# Power.net
KiCad netlist of a schematic drawn in Altium Designer
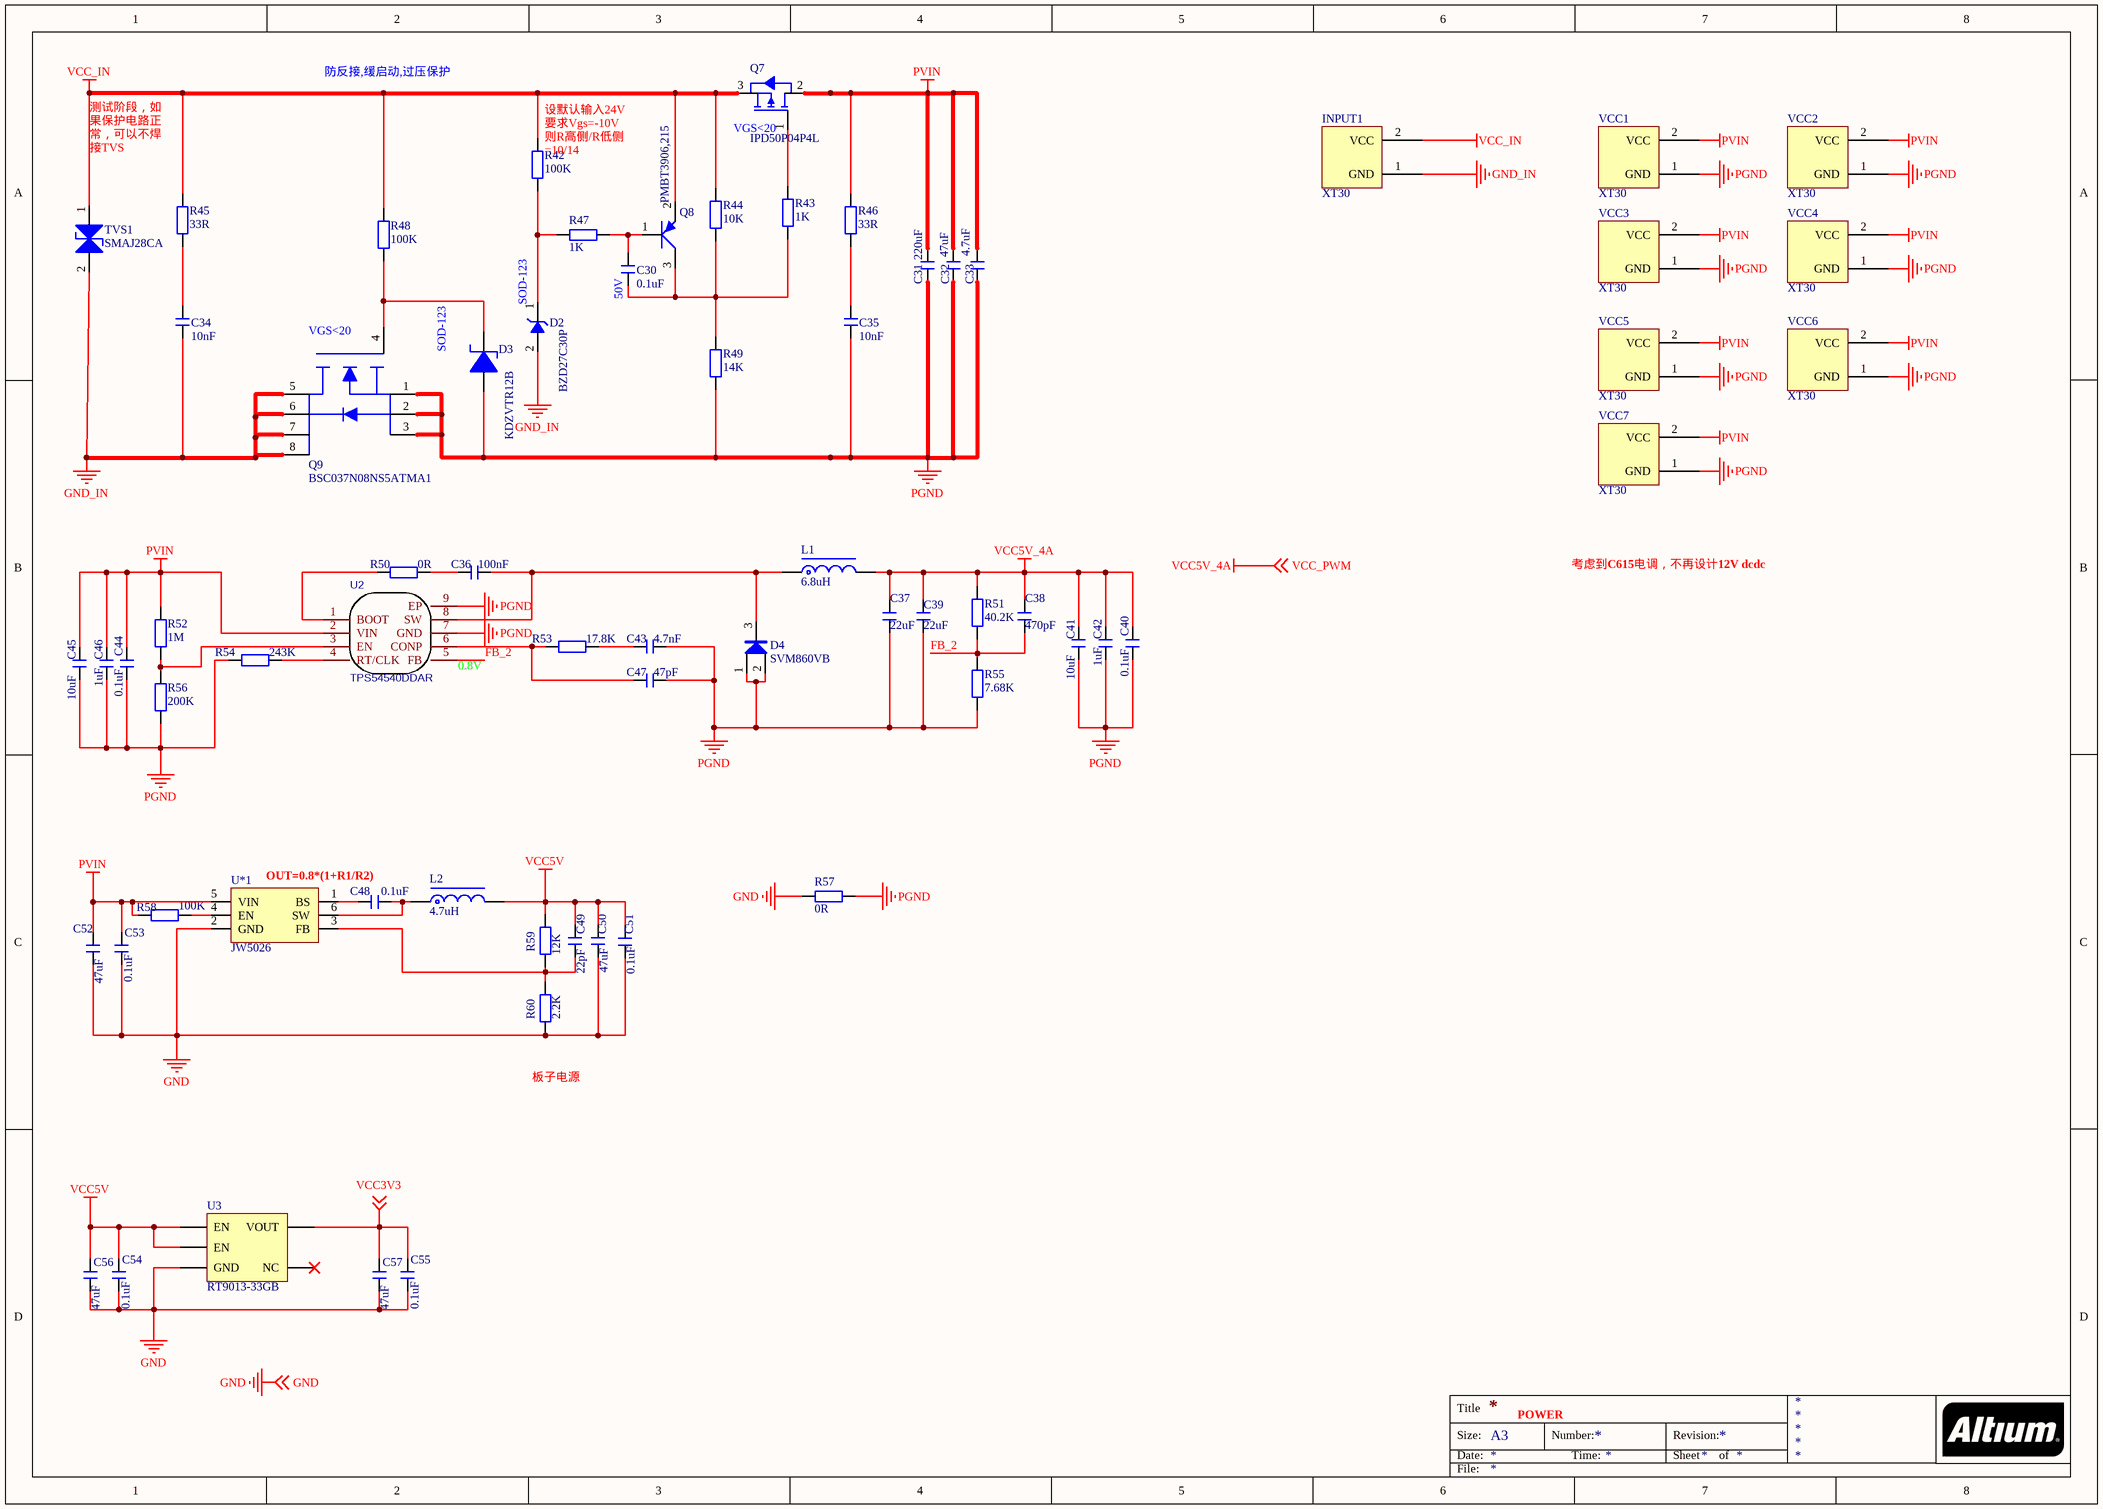
[diagram p0: Power.SchDoc]

(export (version "E")
  (design (tool "Eeschema 10.0.6"))
  (components
    (comp (ref "C30")
      (value "0.1uF")
      (footprint "C 0603_L")
      (description "贴片电容")
      (libsource (lib "0.1 - 电阻-电容-电感") (part "C"))
    )
    (comp (ref "C31")
      (value "220uF")
      (footprint "C 1206_L")
      (description "贴片电容")
      (libsource (lib "0.1 - 电阻-电容-电感") (part "C"))
    )
    (comp (ref "C32")
      (value "47uF")
      (footprint "C 1206_L")
      (description "贴片电容")
      (libsource (lib "0.1 - 电阻-电容-电感") (part "C"))
    )
    (comp (ref "C33")
      (value "4.7uF")
      (footprint "C 1206_L")
      (description "贴片电容")
      (libsource (lib "0.1 - 电阻-电容-电感") (part "C"))
    )
    (comp (ref "C34")
      (value "10nF")
      (footprint "C 0603_L")
      (description "贴片电容")
      (libsource (lib "0.1 - 电阻-电容-电感") (part "C"))
    )
    (comp (ref "C35")
      (value "10nF")
      (footprint "C 0603_L")
      (description "贴片电容")
      (libsource (lib "0.1 - 电阻-电容-电感") (part "C"))
    )
    (comp (ref "C36")
      (value "100nF")
      (footprint "C 0603_L")
      (description "贴片电容")
      (libsource (lib "0.1 - 电阻-电容-电感") (part "C"))
    )
    (comp (ref "C37")
      (value "22uF")
      (footprint "C 0805_L")
      (description "贴片电容")
      (libsource (lib "0.1 - 电阻-电容-电感") (part "C"))
    )
    (comp (ref "C38")
      (value "470pF")
      (footprint "C 0603_L")
      (description "贴片电容")
      (libsource (lib "0.1 - 电阻-电容-电感") (part "C"))
    )
    (comp (ref "C39")
      (value "22uF")
      (footprint "C 0805_L")
      (description "贴片电容")
      (libsource (lib "0.1 - 电阻-电容-电感") (part "C"))
    )
    (comp (ref "C40")
      (value "0.1uF")
      (footprint "C 0805_L")
      (description "贴片电容")
      (libsource (lib "0.1 - 电阻-电容-电感") (part "C"))
    )
    (comp (ref "C41")
      (value "10uF")
      (footprint "C 0805_L")
      (description "贴片电容")
      (libsource (lib "0.1 - 电阻-电容-电感") (part "C"))
    )
    (comp (ref "C42")
      (value "1uF")
      (footprint "C 0805_L")
      (description "贴片电容")
      (libsource (lib "0.1 - 电阻-电容-电感") (part "C"))
    )
    (comp (ref "C43")
      (value "4.7nF")
      (footprint "C 0603_L")
      (description "贴片电容")
      (libsource (lib "0.1 - 电阻-电容-电感") (part "C"))
    )
    (comp (ref "C44")
      (value "0.1uF")
      (footprint "C 0805_L")
      (description "贴片电容")
      (libsource (lib "0.1 - 电阻-电容-电感") (part "C"))
    )
    (comp (ref "C45")
      (value "10uF")
      (footprint "C 0805_L")
      (description "贴片电容")
      (libsource (lib "0.1 - 电阻-电容-电感") (part "C"))
    )
    (comp (ref "C46")
      (value "1uF")
      (footprint "C 0805_L")
      (description "贴片电容")
      (libsource (lib "0.1 - 电阻-电容-电感") (part "C"))
    )
    (comp (ref "C47")
      (value "47pF")
      (footprint "C 0603_L")
      (description "贴片电容")
      (libsource (lib "0.1 - 电阻-电容-电感") (part "C"))
    )
    (comp (ref "C48")
      (value "0.1uF")
      (footprint "C 0603_L")
      (description "贴片电容")
      (libsource (lib "0.1 - 电阻-电容-电感") (part "C"))
    )
    (comp (ref "C49")
      (value "22pF")
      (footprint "C 0603_L")
      (description "贴片电容")
      (libsource (lib "0.1 - 电阻-电容-电感") (part "C"))
    )
    (comp (ref "C50")
      (value "47uF")
      (footprint "C 0805_L")
      (description "贴片电容")
      (libsource (lib "0.1 - 电阻-电容-电感") (part "C"))
    )
    (comp (ref "C51")
      (value "0.1uF")
      (footprint "C 0805_L")
      (description "贴片电容")
      (libsource (lib "0.1 - 电阻-电容-电感") (part "C"))
    )
    (comp (ref "C52")
      (value "47uF")
      (footprint "C 0805_L")
      (description "贴片电容")
      (libsource (lib "0.1 - 电阻-电容-电感") (part "C"))
    )
    (comp (ref "C53")
      (value "0.1uF")
      (footprint "C 0805_L")
      (description "贴片电容")
      (libsource (lib "0.1 - 电阻-电容-电感") (part "C"))
    )
    (comp (ref "C54")
      (value "0.1uF")
      (footprint "C 0805_L")
      (description "贴片电容")
      (libsource (lib "0.1 - 电阻-电容-电感") (part "C"))
    )
    (comp (ref "C55")
      (value "0.1uF")
      (footprint "C 0805_L")
      (description "贴片电容")
      (libsource (lib "0.1 - 电阻-电容-电感") (part "C"))
    )
    (comp (ref "C56")
      (value "47uF")
      (footprint "C 0805_L")
      (description "贴片电容")
      (libsource (lib "0.1 - 电阻-电容-电感") (part "C"))
    )
    (comp (ref "C57")
      (value "47uF")
      (footprint "C 0805_L")
      (description "贴片电容")
      (libsource (lib "0.1 - 电阻-电容-电感") (part "C"))
    )
    (comp (ref "D2")
      (value "BZD27C30P")
      (footprint "mx_pcb_library:SOD-123_L2.8-W1.8-LS3.7-RD")
      (libsource (lib "mx_pcb_library") (part "BZD27C30P"))
    )
    (comp (ref "D3")
      (value "KDZVTR12B")
      (footprint "mx_pcb_library:SOD-123_L2.8-W1.8-LS3.7-RD")
      (libsource (lib "mx_pcb_library") (part "KDZVTR12B"))
    )
    (comp (ref "D4")
      (value "SVM860VB")
      (footprint "1.30-二极管-整流桥堆:TO-277B_3P-L6.1-W4.3-LS7.0-BR")
      (description "TO-277B系列,SVM860VB-8A")
      (libsource (lib "0.2 -  二极管-整流桥") (part "SVM860VB"))
    )
    (comp (ref "INPUT1")
      (value "XT30")
      (footprint "mx_pcb_library:XT30PW-M")
      (libsource (lib "mx_pcb_library") (part "XT30"))
    )
    (comp (ref "L1")
      (value "6.8uH")
      (footprint "CDRH73")
      (description "功率屏蔽电感")
      (libsource (lib "0.1 - 电阻-电容-电感") (part "L-CDRH"))
    )
    (comp (ref "L2")
      (value "4.7uH")
      (footprint "CD53")
      (description "CD系列贴片线绕功率电感")
      (libsource (lib "0.1 - 电阻-电容-电感") (part "L-SMD"))
    )
    (comp (ref "Q7")
      (value "IPD50P04P4L")
      (footprint "mx_pcb_library:PG-TO252-3")
      (libsource (lib "mx_pcb_library") (part "IPD50P04P4L"))
    )
    (comp (ref "Q8")
      (value "PMBT3906,215")
      (footprint "mx_pcb_library:SOT-23-3_L2.9-W1.3-P1.90-LS2.4-BR")
      (libsource (lib "mx_pcb_library") (part "PMBT3906,215"))
    )
    (comp (ref "Q9")
      (value "BSC037N08NS5ATMA1")
      (footprint "mx_pcb_library:PG-TDSON-8_L5.0-W6.0-P1.27-LS6.2-BL-EP")
      (libsource (lib "mx_pcb_library") (part "BSC037N08NS5ATMA1"))
    )
    (comp (ref "R42")
      (value "100K")
      (footprint "R 0603_L")
      (description "贴片电阻")
      (libsource (lib "0.1 - 电阻-电容-电感") (part "R"))
    )
    (comp (ref "R43")
      (value "1K")
      (footprint "R 0603_L")
      (description "贴片电阻")
      (libsource (lib "0.1 - 电阻-电容-电感") (part "R"))
    )
    (comp (ref "R44")
      (value "10K")
      (footprint "R 0603_L")
      (description "贴片电阻")
      (libsource (lib "0.1 - 电阻-电容-电感") (part "R"))
    )
    (comp (ref "R45")
      (value "33R")
      (footprint "R 0603_L")
      (description "贴片电阻")
      (libsource (lib "0.1 - 电阻-电容-电感") (part "R"))
    )
    (comp (ref "R46")
      (value "33R")
      (footprint "R 0603_L")
      (description "贴片电阻")
      (libsource (lib "0.1 - 电阻-电容-电感") (part "R"))
    )
    (comp (ref "R47")
      (value "1K")
      (footprint "R 0603_L")
      (description "贴片电阻")
      (libsource (lib "0.1 - 电阻-电容-电感") (part "R"))
    )
    (comp (ref "R48")
      (value "100K")
      (footprint "R 0603_L")
      (description "贴片电阻")
      (libsource (lib "0.1 - 电阻-电容-电感") (part "R"))
    )
    (comp (ref "R49")
      (value "14K")
      (footprint "R 0603_L")
      (description "贴片电阻")
      (libsource (lib "0.1 - 电阻-电容-电感") (part "R"))
    )
    (comp (ref "R50")
      (value "0R")
      (footprint "R 0603_L")
      (description "贴片电阻")
      (libsource (lib "0.1 - 电阻-电容-电感") (part "R"))
    )
    (comp (ref "R51")
      (value "40.2K")
      (footprint "R 0603_L")
      (description "贴片电阻")
      (libsource (lib "0.1 - 电阻-电容-电感") (part "R"))
    )
    (comp (ref "R52")
      (value "1M")
      (footprint "R 0603_L")
      (description "贴片电阻")
      (libsource (lib "0.1 - 电阻-电容-电感") (part "R"))
    )
    (comp (ref "R53")
      (value "17.8K")
      (footprint "R 0603_L")
      (description "贴片电阻")
      (libsource (lib "0.1 - 电阻-电容-电感") (part "R"))
    )
    (comp (ref "R54")
      (value "243K")
      (footprint "R 0603_L")
      (description "贴片电阻")
      (libsource (lib "0.1 - 电阻-电容-电感") (part "R"))
    )
    (comp (ref "R55")
      (value "7.68K")
      (footprint "R 0603_L")
      (description "贴片电阻")
      (libsource (lib "0.1 - 电阻-电容-电感") (part "R"))
    )
    (comp (ref "R56")
      (value "200K")
      (footprint "R 0603_L")
      (description "贴片电阻")
      (libsource (lib "0.1 - 电阻-电容-电感") (part "R"))
    )
    (comp (ref "R57")
      (value "0R")
      (footprint "R 0603_L")
      (description "贴片电阻")
      (libsource (lib "0.1 - 电阻-电容-电感") (part "R"))
    )
    (comp (ref "R58")
      (value "100K")
      (footprint "R 0603_L")
      (description "贴片电阻")
      (libsource (lib "0.1 - 电阻-电容-电感") (part "R"))
    )
    (comp (ref "R59")
      (value "12K")
      (footprint "R 0603_L")
      (description "贴片电阻")
      (libsource (lib "0.1 - 电阻-电容-电感") (part "R"))
    )
    (comp (ref "R60")
      (value "2.2K")
      (footprint "R 0603_L")
      (description "贴片电阻")
      (libsource (lib "0.1 - 电阻-电容-电感") (part "R"))
    )
    (comp (ref "TVS1")
      (value "SMAJ28CA")
      (footprint "mx_pcb_library:SMA(DO-214AC)")
      (libsource (lib "mx_pcb_library") (part "SMAJ28CA"))
    )
    (comp (ref "U*1")
      (value "JW5026")
      (footprint "SOT-23-6_L2.9-W1.6-P0.95-LS2.8-BL")
      (description "BUCK、MAX40V")
      (libsource (lib "mx_pcb_library") (part "JW5026"))
    )
    (comp (ref "U2")
      (value "TPS54540DDAR")
      (footprint "mx_pcb_library:TPS54540")
      (fields (field (name "BOM_SUPPLIER PART") "C95286"))
      (libsource (lib "mx_pcb_library") (part "TPS54540DDAR"))
    )
    (comp (ref "U3")
      (value "RT9013-33GB")
      (footprint "SOT23-5M")
      (libsource (lib "mx_pcb_library") (part "RT9013-33GB"))
    )
    (comp (ref "VCC1")
      (value "XT30")
      (footprint "mx_pcb_library:XT30UPB-F")
      (libsource (lib "mx_pcb_library") (part "XT30"))
    )
    (comp (ref "VCC2")
      (value "XT30")
      (footprint "mx_pcb_library:XT30UPB-F")
      (libsource (lib "mx_pcb_library") (part "XT30"))
    )
    (comp (ref "VCC3")
      (value "XT30")
      (footprint "mx_pcb_library:XT30UPB-F")
      (libsource (lib "mx_pcb_library") (part "XT30"))
    )
    (comp (ref "VCC4")
      (value "XT30")
      (footprint "mx_pcb_library:XT30UPB-F")
      (libsource (lib "mx_pcb_library") (part "XT30"))
    )
    (comp (ref "VCC5")
      (value "XT30")
      (footprint "mx_pcb_library:XT30UPB-F")
      (libsource (lib "mx_pcb_library") (part "XT30"))
    )
    (comp (ref "VCC6")
      (value "XT30")
      (footprint "mx_pcb_library:XT30UPB-F")
      (libsource (lib "mx_pcb_library") (part "XT30"))
    )
    (comp (ref "VCC7")
      (value "XT30")
      (footprint "mx_pcb_library:XT30UPB-F")
      (libsource (lib "mx_pcb_library") (part "XT30"))
    )
  )
  (nets
    (net (code "1") (name "/FB_2") (class "Default")
      (node (ref "C38") (pin "1") (pinfunction "1_1") (pintype "passive"))
      (node (ref "R51") (pin "1") (pinfunction "1_1") (pintype "passive"))
      (node (ref "R55") (pin "2") (pinfunction "2_2") (pintype "passive"))
      (node (ref "U2") (pin "5") (pinfunction "FB_5") (pintype "passive"))
    )
    (net (code "2") (name "GND") (class "Default")
      (node (ref "C50") (pin "1") (pinfunction "1_1") (pintype "passive"))
      (node (ref "C51") (pin "1") (pinfunction "1_1") (pintype "passive"))
      (node (ref "C52") (pin "1") (pinfunction "1_1") (pintype "passive"))
      (node (ref "C53") (pin "1") (pinfunction "1_1") (pintype "passive"))
      (node (ref "C54") (pin "1") (pinfunction "1_1") (pintype "passive"))
      (node (ref "C55") (pin "1") (pinfunction "1_1") (pintype "passive"))
      (node (ref "C56") (pin "1") (pinfunction "1_1") (pintype "passive"))
      (node (ref "C57") (pin "1") (pinfunction "1_1") (pintype "passive"))
      (node (ref "R57") (pin "1") (pinfunction "1_1") (pintype "passive"))
      (node (ref "R60") (pin "1") (pinfunction "1_1") (pintype "passive"))
      (node (ref "U*1") (pin "2") (pinfunction "GND_2") (pintype "passive"))
      (node (ref "U3") (pin "2") (pinfunction "GND_2") (pintype "passive"))
    )
    (net (code "3") (name "GND_IN") (class "Default")
      (node (ref "C34") (pin "1") (pinfunction "1_1") (pintype "passive"))
      (node (ref "D2") (pin "2") (pinfunction "2_2") (pintype "passive"))
      (node (ref "INPUT1") (pin "1") (pinfunction "GND_1") (pintype "passive"))
      (node (ref "Q9") (pin "5") (pinfunction "5_5") (pintype "passive"))
      (node (ref "Q9") (pin "6") (pinfunction "6_6") (pintype "passive"))
      (node (ref "Q9") (pin "7") (pinfunction "7_7") (pintype "passive"))
      (node (ref "Q9") (pin "8") (pinfunction "8_8") (pintype "passive"))
      (node (ref "TVS1") (pin "2") (pinfunction "2_2") (pintype "passive"))
    )
    (net (code "4") (name "Net-(C30-Pad1)") (class "Default")
      (node (ref "C30") (pin "1") (pinfunction "1_1") (pintype "passive"))
      (node (ref "Q8") (pin "3") (pinfunction "3_3") (pintype "passive"))
      (node (ref "R43") (pin "1") (pinfunction "1_1") (pintype "passive"))
      (node (ref "R44") (pin "1") (pinfunction "1_1") (pintype "passive"))
      (node (ref "R49") (pin "2") (pinfunction "2_2") (pintype "passive"))
    )
    (net (code "5") (name "Net-(C30-Pad2)") (class "Default")
      (node (ref "C30") (pin "2") (pinfunction "2_2") (pintype "passive"))
      (node (ref "Q8") (pin "1") (pinfunction "1_1") (pintype "passive"))
      (node (ref "R47") (pin "1") (pinfunction "1_1") (pintype "passive"))
    )
    (net (code "6") (name "Net-(C34-Pad2)") (class "Default")
      (node (ref "C34") (pin "2") (pinfunction "2_2") (pintype "passive"))
      (node (ref "R45") (pin "1") (pinfunction "1_1") (pintype "passive"))
    )
    (net (code "7") (name "Net-(C35-Pad2)") (class "Default")
      (node (ref "C35") (pin "2") (pinfunction "2_2") (pintype "passive"))
      (node (ref "R46") (pin "1") (pinfunction "1_1") (pintype "passive"))
    )
    (net (code "8") (name "Net-(C36-Pad1)") (class "Default")
      (node (ref "C36") (pin "1") (pinfunction "1_1") (pintype "passive"))
      (node (ref "R50") (pin "1") (pinfunction "1_1") (pintype "passive"))
    )
    (net (code "9") (name "Net-(C43-Pad1)") (class "Default")
      (node (ref "C43") (pin "1") (pinfunction "1_1") (pintype "passive"))
      (node (ref "R53") (pin "1") (pinfunction "1_1") (pintype "passive"))
    )
    (net (code "10") (name "Net-(D2-Pad1)") (class "Default")
      (node (ref "D2") (pin "1") (pinfunction "1_1") (pintype "passive"))
      (node (ref "R42") (pin "1") (pinfunction "1_1") (pintype "passive"))
      (node (ref "R47") (pin "2") (pinfunction "2_2") (pintype "passive"))
    )
    (net (code "11") (name "Net-(D3-Pad1)") (class "Default")
      (node (ref "D3") (pin "1") (pinfunction "1_1") (pintype "passive"))
      (node (ref "Q9") (pin "4") (pinfunction "4_4") (pintype "passive"))
      (node (ref "R48") (pin "1") (pinfunction "1_1") (pintype "passive"))
    )
    (net (code "12") (name "Net-(Q7-Pad1)") (class "Default")
      (node (ref "Q7") (pin "1") (pinfunction "1_1") (pintype "passive"))
      (node (ref "R43") (pin "2") (pinfunction "2_2") (pintype "passive"))
    )
    (net (code "13") (name "Net-(U*1-BS)") (class "Default")
      (node (ref "C48") (pin "1") (pinfunction "1_1") (pintype "passive"))
      (node (ref "U*1") (pin "1") (pinfunction "BS_1") (pintype "passive"))
    )
    (net (code "14") (name "Net-(U*1-EN)") (class "Default")
      (node (ref "R58") (pin "1") (pinfunction "1_1") (pintype "passive"))
      (node (ref "U*1") (pin "4") (pinfunction "EN_4") (pintype "passive"))
    )
    (net (code "15") (name "Net-(U*1-FB)") (class "Default")
      (node (ref "C49") (pin "1") (pinfunction "1_1") (pintype "passive"))
      (node (ref "R59") (pin "1") (pinfunction "1_1") (pintype "passive"))
      (node (ref "R60") (pin "2") (pinfunction "2_2") (pintype "passive"))
      (node (ref "U*1") (pin "3") (pinfunction "FB_3") (pintype "passive"))
    )
    (net (code "16") (name "Net-(U*1-SW)") (class "Default")
      (node (ref "C48") (pin "2") (pinfunction "2_2") (pintype "passive"))
      (node (ref "L2") (pin "1") (pinfunction "1_1") (pintype "passive"))
      (node (ref "U*1") (pin "6") (pinfunction "SW_6") (pintype "passive"))
    )
    (net (code "17") (name "Net-(U2-BOOT)") (class "Default")
      (node (ref "R50") (pin "2") (pinfunction "2_2") (pintype "passive"))
      (node (ref "U2") (pin "1") (pinfunction "BOOT_1") (pintype "passive"))
    )
    (net (code "18") (name "Net-(U2-CONP)") (class "Default")
      (node (ref "C47") (pin "1") (pinfunction "1_1") (pintype "passive"))
      (node (ref "R53") (pin "2") (pinfunction "2_2") (pintype "passive"))
      (node (ref "U2") (pin "6") (pinfunction "CONP_6") (pintype "passive"))
    )
    (net (code "19") (name "Net-(U2-EN)") (class "Default")
      (node (ref "R52") (pin "1") (pinfunction "1_1") (pintype "passive"))
      (node (ref "R56") (pin "2") (pinfunction "2_2") (pintype "passive"))
      (node (ref "U2") (pin "3") (pinfunction "EN_3") (pintype "passive"))
    )
    (net (code "20") (name "Net-(U2-RT{slash}CLK)") (class "Default")
      (node (ref "R54") (pin "1") (pinfunction "1_1") (pintype "passive"))
      (node (ref "U2") (pin "4") (pinfunction "RT/CLK_4") (pintype "passive"))
    )
    (net (code "21") (name "Net-(U2-SW)") (class "Default")
      (node (ref "C36") (pin "2") (pinfunction "2_2") (pintype "passive"))
      (node (ref "D4") (pin "3") (pinfunction "3_3") (pintype "passive"))
      (node (ref "L1") (pin "1") (pinfunction "1_1") (pintype "passive"))
      (node (ref "U2") (pin "8") (pinfunction "SW_8") (pintype "passive"))
    )
    (net (code "22") (name "PGND") (class "Default")
      (node (ref "C31") (pin "1") (pinfunction "1_1") (pintype "passive"))
      (node (ref "C32") (pin "1") (pinfunction "1_1") (pintype "passive"))
      (node (ref "C33") (pin "1") (pinfunction "1_1") (pintype "passive"))
      (node (ref "C35") (pin "1") (pinfunction "1_1") (pintype "passive"))
      (node (ref "C37") (pin "1") (pinfunction "1_1") (pintype "passive"))
      (node (ref "C39") (pin "1") (pinfunction "1_1") (pintype "passive"))
      (node (ref "C40") (pin "1") (pinfunction "1_1") (pintype "passive"))
      (node (ref "C41") (pin "1") (pinfunction "1_1") (pintype "passive"))
      (node (ref "C42") (pin "1") (pinfunction "1_1") (pintype "passive"))
      (node (ref "C43") (pin "2") (pinfunction "2_2") (pintype "passive"))
      (node (ref "C44") (pin "1") (pinfunction "1_1") (pintype "passive"))
      (node (ref "C45") (pin "1") (pinfunction "1_1") (pintype "passive"))
      (node (ref "C46") (pin "1") (pinfunction "1_1") (pintype "passive"))
      (node (ref "C47") (pin "2") (pinfunction "2_2") (pintype "passive"))
      (node (ref "D3") (pin "2") (pinfunction "2_2") (pintype "passive"))
      (node (ref "D4") (pin "1") (pinfunction "A_1") (pintype "passive"))
      (node (ref "D4") (pin "2") (pinfunction "K_2") (pintype "passive"))
      (node (ref "Q9") (pin "1") (pinfunction "1_1") (pintype "passive"))
      (node (ref "Q9") (pin "2") (pinfunction "2_2") (pintype "passive"))
      (node (ref "Q9") (pin "3") (pinfunction "3_3") (pintype "passive"))
      (node (ref "R49") (pin "1") (pinfunction "1_1") (pintype "passive"))
      (node (ref "R54") (pin "2") (pinfunction "2_2") (pintype "passive"))
      (node (ref "R55") (pin "1") (pinfunction "1_1") (pintype "passive"))
      (node (ref "R56") (pin "1") (pinfunction "1_1") (pintype "passive"))
      (node (ref "R57") (pin "2") (pinfunction "2_2") (pintype "passive"))
      (node (ref "U2") (pin "7") (pinfunction "GND_7") (pintype "passive"))
      (node (ref "U2") (pin "9") (pinfunction "EP_9") (pintype "passive"))
      (node (ref "VCC1") (pin "1") (pinfunction "GND_1") (pintype "passive"))
      (node (ref "VCC2") (pin "1") (pinfunction "GND_1") (pintype "passive"))
      (node (ref "VCC3") (pin "1") (pinfunction "GND_1") (pintype "passive"))
      (node (ref "VCC4") (pin "1") (pinfunction "GND_1") (pintype "passive"))
      (node (ref "VCC5") (pin "1") (pinfunction "GND_1") (pintype "passive"))
      (node (ref "VCC6") (pin "1") (pinfunction "GND_1") (pintype "passive"))
      (node (ref "VCC7") (pin "1") (pinfunction "GND_1") (pintype "passive"))
    )
    (net (code "23") (name "PVIN") (class "Default")
      (node (ref "C31") (pin "2") (pinfunction "2_2") (pintype "passive"))
      (node (ref "C32") (pin "2") (pinfunction "2_2") (pintype "passive"))
      (node (ref "C33") (pin "2") (pinfunction "2_2") (pintype "passive"))
      (node (ref "C44") (pin "2") (pinfunction "2_2") (pintype "passive"))
      (node (ref "C45") (pin "2") (pinfunction "2_2") (pintype "passive"))
      (node (ref "C46") (pin "2") (pinfunction "2_2") (pintype "passive"))
      (node (ref "C52") (pin "2") (pinfunction "2_2") (pintype "passive"))
      (node (ref "C53") (pin "2") (pinfunction "2_2") (pintype "passive"))
      (node (ref "Q7") (pin "2") (pinfunction "2_2") (pintype "passive"))
      (node (ref "R46") (pin "2") (pinfunction "2_2") (pintype "passive"))
      (node (ref "R52") (pin "2") (pinfunction "2_2") (pintype "passive"))
      (node (ref "R58") (pin "2") (pinfunction "2_2") (pintype "passive"))
      (node (ref "U*1") (pin "5") (pinfunction "VIN_5") (pintype "passive"))
      (node (ref "U2") (pin "2") (pinfunction "VIN_2") (pintype "passive"))
      (node (ref "VCC1") (pin "2") (pinfunction "VCC_2") (pintype "passive"))
      (node (ref "VCC2") (pin "2") (pinfunction "VCC_2") (pintype "passive"))
      (node (ref "VCC3") (pin "2") (pinfunction "VCC_2") (pintype "passive"))
      (node (ref "VCC4") (pin "2") (pinfunction "VCC_2") (pintype "passive"))
      (node (ref "VCC5") (pin "2") (pinfunction "VCC_2") (pintype "passive"))
      (node (ref "VCC6") (pin "2") (pinfunction "VCC_2") (pintype "passive"))
      (node (ref "VCC7") (pin "2") (pinfunction "VCC_2") (pintype "passive"))
    )
    (net (code "24") (name "VCC3V3") (class "Default")
      (node (ref "C55") (pin "2") (pinfunction "2_2") (pintype "passive"))
      (node (ref "C57") (pin "2") (pinfunction "2_2") (pintype "passive"))
      (node (ref "U3") (pin "5") (pinfunction "VOUT_5") (pintype "passive"))
    )
    (net (code "25") (name "VCC5V") (class "Default")
      (node (ref "C49") (pin "2") (pinfunction "2_2") (pintype "passive"))
      (node (ref "C50") (pin "2") (pinfunction "2_2") (pintype "passive"))
      (node (ref "C51") (pin "2") (pinfunction "2_2") (pintype "passive"))
      (node (ref "C54") (pin "2") (pinfunction "2_2") (pintype "passive"))
      (node (ref "C56") (pin "2") (pinfunction "2_2") (pintype "passive"))
      (node (ref "L2") (pin "2") (pinfunction "2_2") (pintype "passive"))
      (node (ref "R59") (pin "2") (pinfunction "2_2") (pintype "passive"))
      (node (ref "U3") (pin "1") (pinfunction "EN_1") (pintype "passive"))
      (node (ref "U3") (pin "3") (pinfunction "EN_3") (pintype "passive"))
    )
    (net (code "26") (name "VCC5V_4A") (class "Default")
      (node (ref "C37") (pin "2") (pinfunction "2_2") (pintype "passive"))
      (node (ref "C38") (pin "2") (pinfunction "2_2") (pintype "passive"))
      (node (ref "C39") (pin "2") (pinfunction "2_2") (pintype "passive"))
      (node (ref "C40") (pin "2") (pinfunction "2_2") (pintype "passive"))
      (node (ref "C41") (pin "2") (pinfunction "2_2") (pintype "passive"))
      (node (ref "C42") (pin "2") (pinfunction "2_2") (pintype "passive"))
      (node (ref "L1") (pin "2") (pinfunction "2_2") (pintype "passive"))
      (node (ref "R51") (pin "2") (pinfunction "2_2") (pintype "passive"))
    )
    (net (code "27") (name "VCC_IN") (class "Default")
      (node (ref "INPUT1") (pin "2") (pinfunction "VCC_2") (pintype "passive"))
      (node (ref "Q7") (pin "3") (pinfunction "3_3") (pintype "passive"))
      (node (ref "Q8") (pin "2") (pinfunction "2_2") (pintype "passive"))
      (node (ref "R42") (pin "2") (pinfunction "2_2") (pintype "passive"))
      (node (ref "R44") (pin "2") (pinfunction "2_2") (pintype "passive"))
      (node (ref "R45") (pin "2") (pinfunction "2_2") (pintype "passive"))
      (node (ref "R48") (pin "2") (pinfunction "2_2") (pintype "passive"))
      (node (ref "TVS1") (pin "1") (pinfunction "1_1") (pintype "passive"))
    )
    (net (code "28") (name "unconnected-(U3-NC-Pad4)") (class "Default")
      (node (ref "U3") (pin "4") (pinfunction "NC_4") (pintype "passive+no_connect"))
    )
  )
)
